# 16_USB_HUB_GL3510.net
KiCad netlist of a schematic drawn in Altium Designer
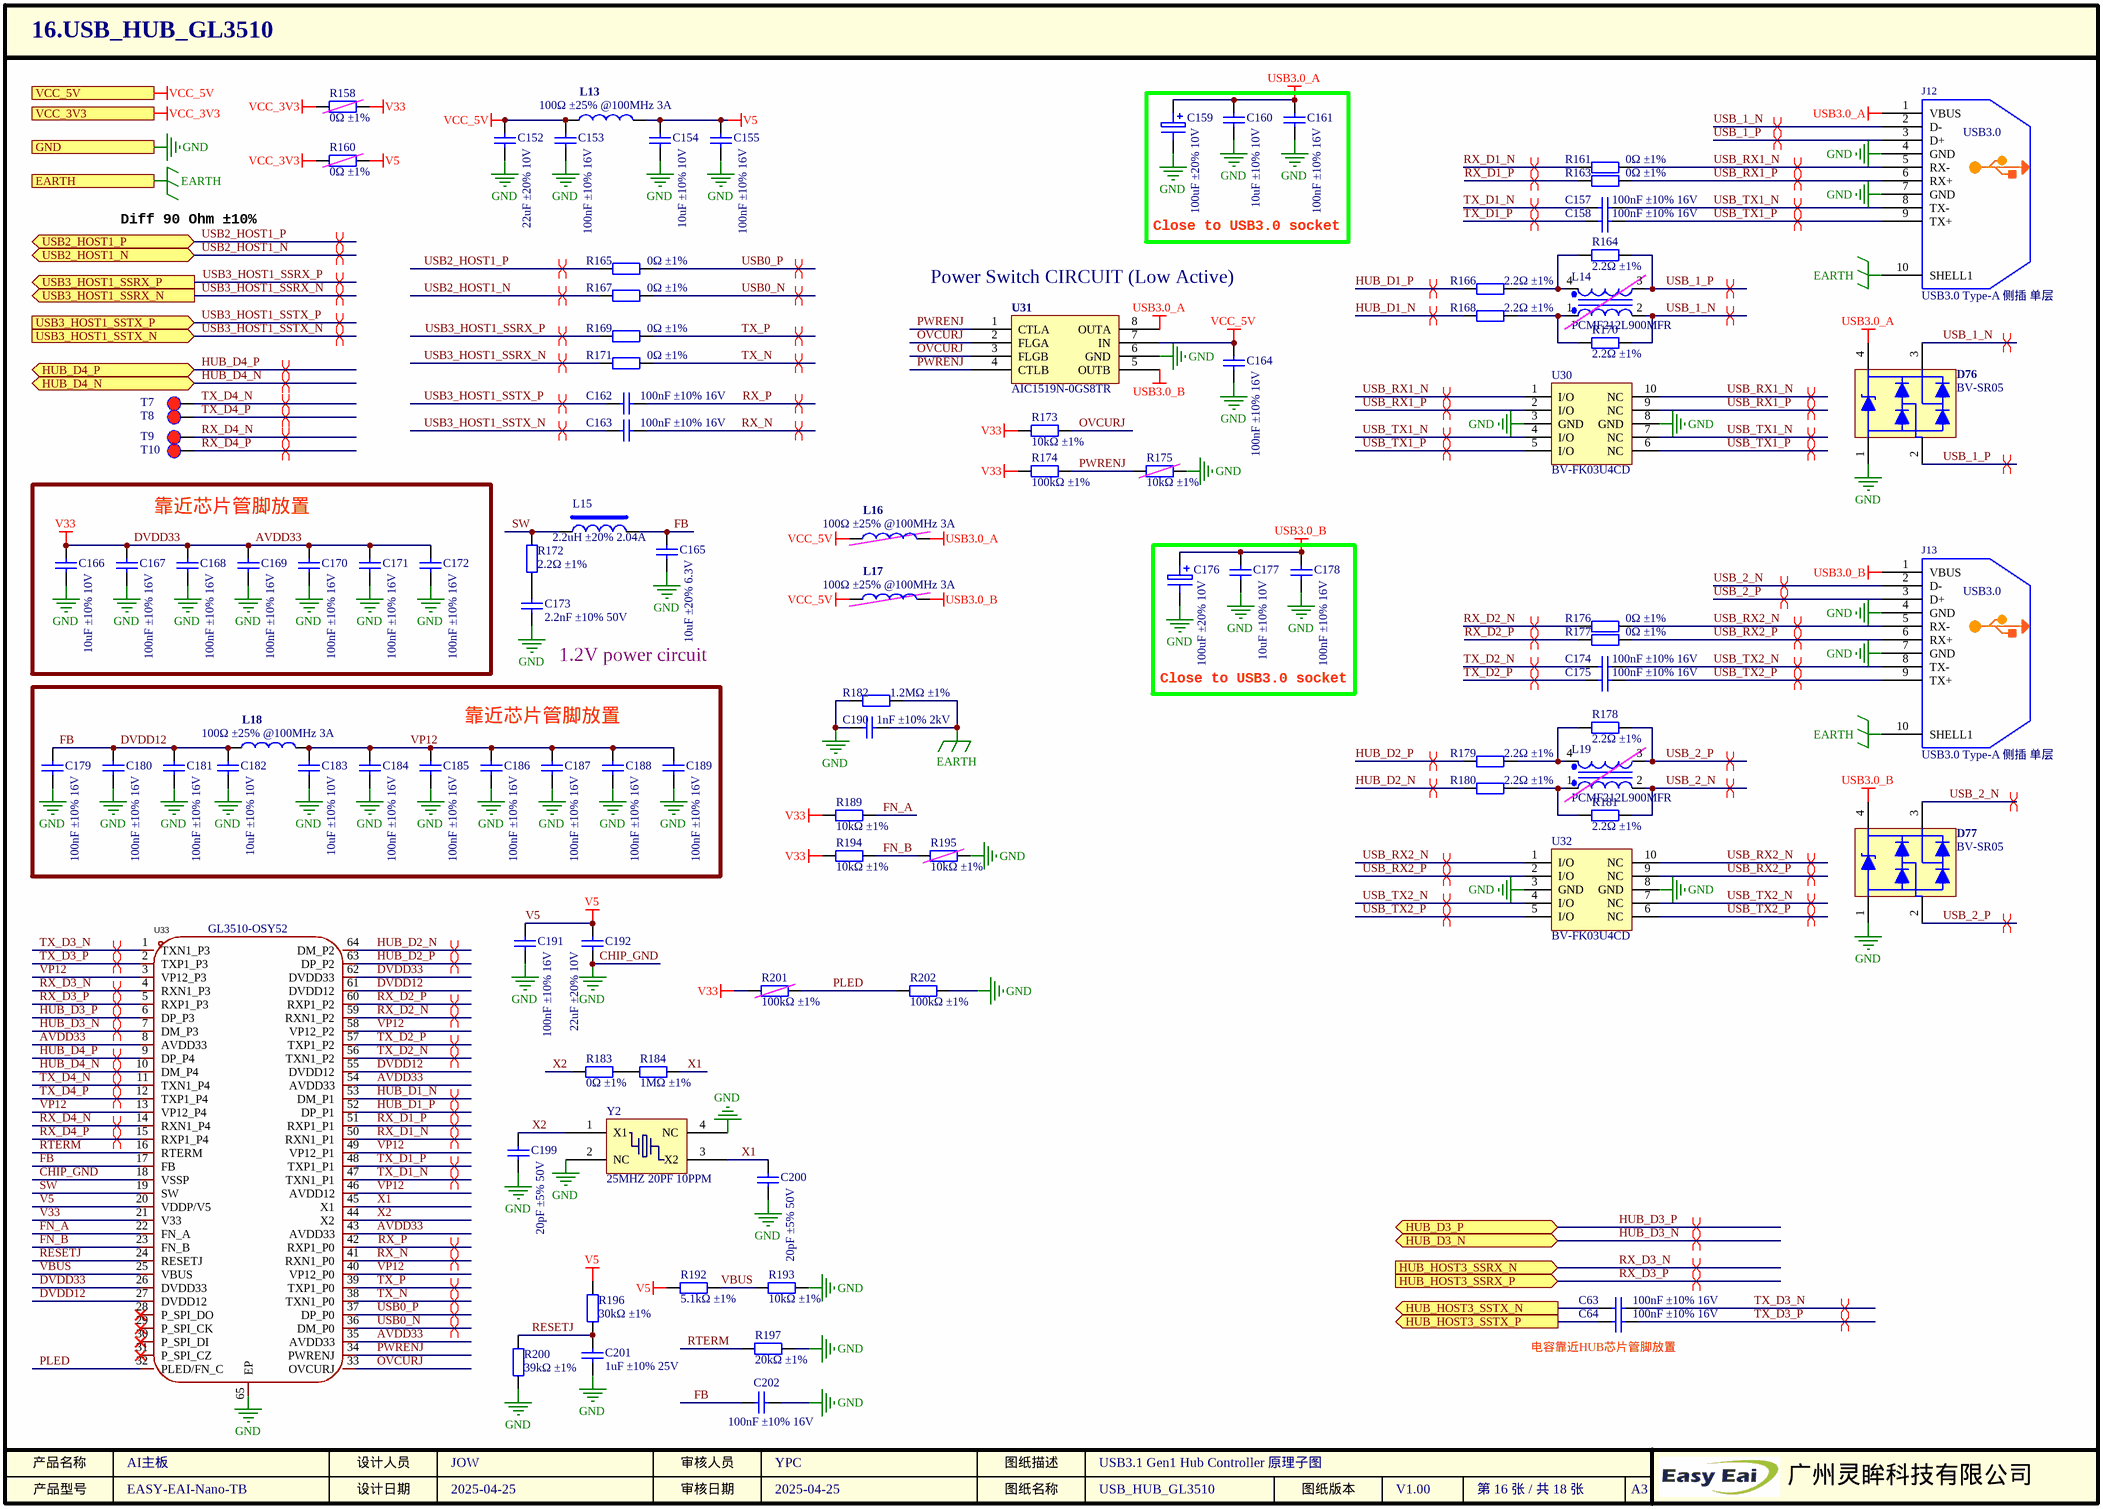
[diagram p0: 16.USB_HUB_GL3510.SchDoc]

(export (version "E")
  (design (tool "Eeschema 10.0.6"))
  (components
    (comp (ref "C63")
      (value "CL05B104KO5NNNC")
      (footprint "0402_C")
      (description "SPZL000259")
      (fields (field (name "描述") "100nF ±10% 16V"))
      (libsource (lib "altium-import") (part "root_2_0402 100nF ±10% 16V_"))
    )
    (comp (ref "C64")
      (value "CL05B104KO5NNNC")
      (footprint "0402_C")
      (description "SPZL000259")
      (fields (field (name "描述") "100nF ±10% 16V"))
      (libsource (lib "altium-import") (part "root_2_0402 100nF ±10% 16V_"))
    )
    (comp (ref "C152")
      (value "CL10A226MP8NUNE")
      (footprint "0603_C")
      (description "SPZL000315")
      (fields (field (name "描述") "22uF ±20% 10V"))
      (libsource (lib "CAP_EASY-EAI") (part "0603 22uF ±20% 10V"))
    )
    (comp (ref "C153")
      (value "CL05B104KO5NNNC")
      (footprint "0402_C")
      (description "SPZL000259")
      (fields (field (name "描述") "100nF ±10% 16V"))
      (libsource (lib "altium-import") (part "root_3_0402 100nF ±10% 16V_"))
    )
    (comp (ref "C154")
      (value "CL10A106KP8NNNC")
      (footprint "0603_C")
      (description "SPZL000260")
      (fields (field (name "描述") "10uF ±10% 10V"))
      (libsource (lib "CAP_EASY-EAI") (part "0603 10uF ±10% 10V"))
    )
    (comp (ref "C155")
      (value "CL05B104KO5NNNC")
      (footprint "0402_C")
      (description "SPZL000259")
      (fields (field (name "描述") "100nF ±10% 16V"))
      (libsource (lib "altium-import") (part "root_3_0402 100nF ±10% 16V_"))
    )
    (comp (ref "C157")
      (value "CL05B104KO5NNNC")
      (footprint "0402_C")
      (description "SPZL000259")
      (fields (field (name "描述") "100nF ±10% 16V"))
      (libsource (lib "altium-import") (part "root_0_0402 100nF ±10% 16V_"))
    )
    (comp (ref "C158")
      (value "CL05B104KO5NNNC")
      (footprint "0402_C")
      (description "SPZL000259")
      (fields (field (name "描述") "100nF ±10% 16V"))
      (libsource (lib "altium-import") (part "root_0_0402 100nF ±10% 16V_"))
    )
    (comp (ref "C159")
      (value "RVT1A101M0505")
      (footprint "SMD,D5xL5.4mm")
      (description "SPZL000265")
      (fields (field (name "描述") "100uF ±20% 10V"))
      (libsource (lib "altium-import") (part "root_0_电解电容 100uF ±20% 10V_"))
    )
    (comp (ref "C160")
      (value "CL10A106KP8NNNC")
      (footprint "0603_C")
      (description "SPZL000260")
      (fields (field (name "描述") "10uF ±10% 10V"))
      (libsource (lib "altium-import") (part "root_1_0603 10uF ±10% 10V_"))
    )
    (comp (ref "C161")
      (value "CL05B104KO5NNNC")
      (footprint "0402_C")
      (description "SPZL000259")
      (fields (field (name "描述") "100nF ±10% 16V"))
      (libsource (lib "altium-import") (part "root_1_0402 100nF ±10% 16V_"))
    )
    (comp (ref "C162")
      (value "CL05B104KO5NNNC")
      (footprint "0402_C")
      (description "SPZL000259")
      (fields (field (name "描述") "100nF ±10% 16V"))
      (libsource (lib "altium-import") (part "root_2_0402 100nF ±10% 16V_"))
    )
    (comp (ref "C163")
      (value "CL05B104KO5NNNC")
      (footprint "0402_C")
      (description "SPZL000259")
      (fields (field (name "描述") "100nF ±10% 16V"))
      (libsource (lib "altium-import") (part "root_2_0402 100nF ±10% 16V_"))
    )
    (comp (ref "C164")
      (value "CL05B104KO5NNNC")
      (footprint "0402_C")
      (description "SPZL000259")
      (fields (field (name "描述") "100nF ±10% 16V"))
      (libsource (lib "altium-import") (part "root_1_0402 100nF ±10% 16V_"))
    )
    (comp (ref "C165")
      (value "CL05A106MQ5NUNC")
      (footprint "0402_C")
      (description "SPZL000269")
      (fields (field (name "描述") "10uF ±20% 6.3V"))
      (libsource (lib "CAP_EASY-EAI") (part "0402 10uF ±20% 6.3V"))
    )
    (comp (ref "C166")
      (value "CL10A106KP8NNNC")
      (footprint "0603_C")
      (description "SPZL000260")
      (fields (field (name "描述") "10uF ±10% 10V"))
      (libsource (lib "CAP_EASY-EAI") (part "0603 10uF ±10% 10V"))
    )
    (comp (ref "C167")
      (value "CL05B104KO5NNNC")
      (footprint "0402_C")
      (description "SPZL000259")
      (fields (field (name "描述") "100nF ±10% 16V"))
      (libsource (lib "altium-import") (part "root_3_0402 100nF ±10% 16V_"))
    )
    (comp (ref "C168")
      (value "CL05B104KO5NNNC")
      (footprint "0402_C")
      (description "SPZL000259")
      (fields (field (name "描述") "100nF ±10% 16V"))
      (libsource (lib "altium-import") (part "root_3_0402 100nF ±10% 16V_"))
    )
    (comp (ref "C169")
      (value "CL05B104KO5NNNC")
      (footprint "0402_C")
      (description "SPZL000259")
      (fields (field (name "描述") "100nF ±10% 16V"))
      (libsource (lib "altium-import") (part "root_3_0402 100nF ±10% 16V_"))
    )
    (comp (ref "C170")
      (value "CL05B104KO5NNNC")
      (footprint "0402_C")
      (description "SPZL000259")
      (fields (field (name "描述") "100nF ±10% 16V"))
      (libsource (lib "altium-import") (part "root_3_0402 100nF ±10% 16V_"))
    )
    (comp (ref "C171")
      (value "CL05B104KO5NNNC")
      (footprint "0402_C")
      (description "SPZL000259")
      (fields (field (name "描述") "100nF ±10% 16V"))
      (libsource (lib "altium-import") (part "root_3_0402 100nF ±10% 16V_"))
    )
    (comp (ref "C172")
      (value "CL05B104KO5NNNC")
      (footprint "0402_C")
      (description "SPZL000259")
      (fields (field (name "描述") "100nF ±10% 16V"))
      (libsource (lib "altium-import") (part "root_3_0402 100nF ±10% 16V_"))
    )
    (comp (ref "C173")
      (value "0402B222K500NT")
      (footprint "0402_C")
      (description "SPZL000399")
      (fields (field (name "描述") "2.2nF ±10% 50V"))
      (libsource (lib "CAP_EASY-EAI") (part "0402 2.2nF ±10% 50V"))
    )
    (comp (ref "C174")
      (value "CL05B104KO5NNNC")
      (footprint "0402_C")
      (description "SPZL000259")
      (fields (field (name "描述") "100nF ±10% 16V"))
      (libsource (lib "altium-import") (part "root_0_0402 100nF ±10% 16V_"))
    )
    (comp (ref "C175")
      (value "CL05B104KO5NNNC")
      (footprint "0402_C")
      (description "SPZL000259")
      (fields (field (name "描述") "100nF ±10% 16V"))
      (libsource (lib "altium-import") (part "root_0_0402 100nF ±10% 16V_"))
    )
    (comp (ref "C176")
      (value "RVT1A101M0505")
      (footprint "SMD,D5xL5.4mm")
      (description "SPZL000265")
      (fields (field (name "描述") "100uF ±20% 10V"))
      (libsource (lib "altium-import") (part "root_0_电解电容 100uF ±20% 10V_"))
    )
    (comp (ref "C177")
      (value "CL10A106KP8NNNC")
      (footprint "0603_C")
      (description "SPZL000260")
      (fields (field (name "描述") "10uF ±10% 10V"))
      (libsource (lib "altium-import") (part "root_1_0603 10uF ±10% 10V_"))
    )
    (comp (ref "C178")
      (value "CL05B104KO5NNNC")
      (footprint "0402_C")
      (description "SPZL000259")
      (fields (field (name "描述") "100nF ±10% 16V"))
      (libsource (lib "altium-import") (part "root_1_0402 100nF ±10% 16V_"))
    )
    (comp (ref "C179")
      (value "CL05B104KO5NNNC")
      (footprint "0402_C")
      (description "SPZL000259")
      (fields (field (name "描述") "100nF ±10% 16V"))
      (libsource (lib "altium-import") (part "root_3_0402 100nF ±10% 16V_"))
    )
    (comp (ref "C180")
      (value "CL05B104KO5NNNC")
      (footprint "0402_C")
      (description "SPZL000259")
      (fields (field (name "描述") "100nF ±10% 16V"))
      (libsource (lib "altium-import") (part "root_3_0402 100nF ±10% 16V_"))
    )
    (comp (ref "C181")
      (value "CL05B104KO5NNNC")
      (footprint "0402_C")
      (description "SPZL000259")
      (fields (field (name "描述") "100nF ±10% 16V"))
      (libsource (lib "altium-import") (part "root_3_0402 100nF ±10% 16V_"))
    )
    (comp (ref "C182")
      (value "CL10A106KP8NNNC")
      (footprint "0603_C")
      (description "SPZL000260")
      (fields (field (name "描述") "10uF ±10% 10V"))
      (libsource (lib "CAP_EASY-EAI") (part "0603 10uF ±10% 10V"))
    )
    (comp (ref "C183")
      (value "CL10A106KP8NNNC")
      (footprint "0603_C")
      (description "SPZL000260")
      (fields (field (name "描述") "10uF ±10% 10V"))
      (libsource (lib "CAP_EASY-EAI") (part "0603 10uF ±10% 10V"))
    )
    (comp (ref "C184")
      (value "CL05B104KO5NNNC")
      (footprint "0402_C")
      (description "SPZL000259")
      (fields (field (name "描述") "100nF ±10% 16V"))
      (libsource (lib "altium-import") (part "root_3_0402 100nF ±10% 16V_"))
    )
    (comp (ref "C185")
      (value "CL05B104KO5NNNC")
      (footprint "0402_C")
      (description "SPZL000259")
      (fields (field (name "描述") "100nF ±10% 16V"))
      (libsource (lib "altium-import") (part "root_3_0402 100nF ±10% 16V_"))
    )
    (comp (ref "C186")
      (value "CL05B104KO5NNNC")
      (footprint "0402_C")
      (description "SPZL000259")
      (fields (field (name "描述") "100nF ±10% 16V"))
      (libsource (lib "altium-import") (part "root_3_0402 100nF ±10% 16V_"))
    )
    (comp (ref "C187")
      (value "CL05B104KO5NNNC")
      (footprint "0402_C")
      (description "SPZL000259")
      (fields (field (name "描述") "100nF ±10% 16V"))
      (libsource (lib "altium-import") (part "root_3_0402 100nF ±10% 16V_"))
    )
    (comp (ref "C188")
      (value "CL05B104KO5NNNC")
      (footprint "0402_C")
      (description "SPZL000259")
      (fields (field (name "描述") "100nF ±10% 16V"))
      (libsource (lib "altium-import") (part "root_3_0402 100nF ±10% 16V_"))
    )
    (comp (ref "C189")
      (value "CL05B104KO5NNNC")
      (footprint "0402_C")
      (description "SPZL000259")
      (fields (field (name "描述") "100nF ±10% 16V"))
      (libsource (lib "altium-import") (part "root_3_0402 100nF ±10% 16V_"))
    )
    (comp (ref "C190")
      (value "CC1206KKX7RDBB102")
      (footprint "1206_C")
      (description "SPZL000332")
      (fields (field (name "描述") "1nF ±10% 2kV"))
      (libsource (lib "altium-import") (part "root_0_1206 1nF ±10% 2kV_"))
    )
    (comp (ref "C191")
      (value "CL05B104KO5NNNC")
      (footprint "0402_C")
      (description "SPZL000259")
      (fields (field (name "描述") "100nF ±10% 16V"))
      (libsource (lib "altium-import") (part "root_3_0402 100nF ±10% 16V_"))
    )
    (comp (ref "C192")
      (value "CL10A226MP8NUNE")
      (footprint "0603_C")
      (description "SPZL000315")
      (fields (field (name "描述") "22uF ±20% 10V"))
      (libsource (lib "CAP_EASY-EAI") (part "0603 22uF ±20% 10V"))
    )
    (comp (ref "C199")
      (value "0402CG200J500NT")
      (footprint "0402_C")
      (description "SPZL000398")
      (fields (field (name "描述") "20pF ±5% 50V"))
      (libsource (lib "CAP_EASY-EAI") (part "0402 20pF ±5% 50V"))
    )
    (comp (ref "C200")
      (value "0402CG200J500NT")
      (footprint "0402_C")
      (description "SPZL000398")
      (fields (field (name "描述") "20pF ±5% 50V"))
      (libsource (lib "CAP_EASY-EAI") (part "0402 20pF ±5% 50V"))
    )
    (comp (ref "C201")
      (value "CL05A105KA5NQNC")
      (footprint "0402_C")
      (description "SPZL000337")
      (fields (field (name "描述") "1uF ±10% 25V"))
      (libsource (lib "CAP_EASY-EAI") (part "0402 1uF ±10% 25V"))
    )
    (comp (ref "C202")
      (value "CL05B104KO5NNNC")
      (footprint "0402_C")
      (description "SPZL000259")
      (fields (field (name "描述") "100nF ±10% 16V"))
      (libsource (lib "altium-import") (part "root_2_0402 100nF ±10% 16V_"))
    )
    (comp (ref "D76")
      (value "BV-SR05")
      (footprint "SOT-143")
      (description "SPZL000616")
      (fields (field (name "型号") "BV-SR05"))
      (libsource (lib "ESD_EASY-EAI") (part "TVS BV-SR05"))
    )
    (comp (ref "D77")
      (value "BV-SR05")
      (footprint "SOT-143")
      (description "SPZL000616")
      (fields (field (name "型号") "BV-SR05"))
      (libsource (lib "ESD_EASY-EAI") (part "TVS BV-SR05"))
    )
    (comp (ref "J12")
      (value "U231-091N-4BLCC14-S5")
      (footprint "USB3.0-A-TH_U231-091N-4BLCC14-S-5")
      (description "SPZL001065")
      (fields (field (name "描述") "USB3.0 Type-A 侧插 单层"))
      (libsource (lib "EASY-EAI-Nano-TB V1.01") (part "USB3.0 Type-A 侧插 单层"))
    )
    (comp (ref "J13")
      (value "U231-091N-4BLCC14-S5")
      (footprint "USB3.0-A-TH_U231-091N-4BLCC14-S-5")
      (description "SPZL001065")
      (fields (field (name "描述") "USB3.0 Type-A 侧插 单层"))
      (libsource (lib "EASY-EAI-Nano-TB V1.01") (part "USB3.0 Type-A 侧插 单层"))
    )
    (comp (ref "L13")
      (value "MPZ1608S101ATAH0")
      (footprint "0603_R")
      (description "SPZL000753")
      (fields (field (name "描述") "100Ω ±25% @100MHz 3A"))
      (libsource (lib "Inductor_EASY-EAI") (part "100Ω ±25% @100MHz 3A"))
    )
    (comp (ref "L14")
      (value "PCMF212L900MFR")
      (footprint "SMD2012")
      (description "SPZL001149")
      (fields (field (name "型号") "PCMF212L900MFR"))
      (libsource (lib "ESD_EASY-EAI") (part "共模电感 PCMF212L900MFR"))
    )
    (comp (ref "L15")
      (value "VLS252012HBX-2R2M-1")
      (footprint "IND_252012")
      (description "SPZL000205")
      (fields (field (name "描述") "2.2uH ±20% 2.04A"))
      (libsource (lib "Inductor_EASY-EAI") (part "2.2uH ±20% 2.04A"))
    )
    (comp (ref "L16")
      (value "MPZ1608S101ATAH0")
      (footprint "0603_R")
      (description "SPZL000753")
      (fields (field (name "描述") "100Ω ±25% @100MHz 3A"))
      (libsource (lib "Inductor_EASY-EAI") (part "100Ω ±25% @100MHz 3A"))
    )
    (comp (ref "L17")
      (value "MPZ1608S101ATAH0")
      (footprint "0603_R")
      (description "SPZL000753")
      (fields (field (name "描述") "100Ω ±25% @100MHz 3A"))
      (libsource (lib "Inductor_EASY-EAI") (part "100Ω ±25% @100MHz 3A"))
    )
    (comp (ref "L18")
      (value "MPZ1608S101ATAH0")
      (footprint "0603_R")
      (description "SPZL000753")
      (fields (field (name "描述") "100Ω ±25% @100MHz 3A"))
      (libsource (lib "Inductor_EASY-EAI") (part "100Ω ±25% @100MHz 3A"))
    )
    (comp (ref "L19")
      (value "PCMF212L900MFR")
      (footprint "SMD2012")
      (description "SPZL001149")
      (fields (field (name "型号") "PCMF212L900MFR"))
      (libsource (lib "ESD_EASY-EAI") (part "共模电感 PCMF212L900MFR"))
    )
    (comp (ref "R158")
      (value "0805W8F0000T5E")
      (footprint "0805_R")
      (description "SPZL000350")
      (fields (field (name "描述") "0Ω ±1%"))
      (libsource (lib "RES_EASY-EAI") (part "0805 0Ω ±1%"))
    )
    (comp (ref "R160")
      (value "0805W8F0000T5E")
      (footprint "0805_R")
      (description "SPZL000350")
      (fields (field (name "描述") "0Ω ±1%"))
      (libsource (lib "RES_EASY-EAI") (part "0805 0Ω ±1%"))
    )
    (comp (ref "R161")
      (value "0402WGF0000TCE")
      (footprint "0402_R")
      (description "SPZL000276")
      (fields (field (name "描述") "0Ω ±1%"))
      (libsource (lib "RES_EASY-EAI") (part "0402 0Ω ±1%"))
    )
    (comp (ref "R163")
      (value "0402WGF0000TCE")
      (footprint "0402_R")
      (description "SPZL000276")
      (fields (field (name "描述") "0Ω ±1%"))
      (libsource (lib "RES_EASY-EAI") (part "0402 0Ω ±1%"))
    )
    (comp (ref "R164")
      (value "0402WGF220KTCE")
      (footprint "0402_R")
      (description "SPZL000327")
      (fields (field (name "描述") "2.2Ω ±1%"))
      (libsource (lib "RES_EASY-EAI") (part "0402 2.2Ω ±1%"))
    )
    (comp (ref "R165")
      (value "0402WGF0000TCE")
      (footprint "0402_R")
      (description "SPZL000276")
      (fields (field (name "描述") "0Ω ±1%"))
      (libsource (lib "RES_EASY-EAI") (part "0402 0Ω ±1%"))
    )
    (comp (ref "R166")
      (value "0402WGF220KTCE")
      (footprint "0402_R")
      (description "SPZL000327")
      (fields (field (name "描述") "2.2Ω ±1%"))
      (libsource (lib "RES_EASY-EAI") (part "0402 2.2Ω ±1%"))
    )
    (comp (ref "R167")
      (value "0402WGF0000TCE")
      (footprint "0402_R")
      (description "SPZL000276")
      (fields (field (name "描述") "0Ω ±1%"))
      (libsource (lib "RES_EASY-EAI") (part "0402 0Ω ±1%"))
    )
    (comp (ref "R168")
      (value "0402WGF220KTCE")
      (footprint "0402_R")
      (description "SPZL000327")
      (fields (field (name "描述") "2.2Ω ±1%"))
      (libsource (lib "RES_EASY-EAI") (part "0402 2.2Ω ±1%"))
    )
    (comp (ref "R169")
      (value "0402WGF0000TCE")
      (footprint "0402_R")
      (description "SPZL000276")
      (fields (field (name "描述") "0Ω ±1%"))
      (libsource (lib "RES_EASY-EAI") (part "0402 0Ω ±1%"))
    )
    (comp (ref "R170")
      (value "0402WGF220KTCE")
      (footprint "0402_R")
      (description "SPZL000327")
      (fields (field (name "描述") "2.2Ω ±1%"))
      (libsource (lib "RES_EASY-EAI") (part "0402 2.2Ω ±1%"))
    )
    (comp (ref "R171")
      (value "0402WGF0000TCE")
      (footprint "0402_R")
      (description "SPZL000276")
      (fields (field (name "描述") "0Ω ±1%"))
      (libsource (lib "RES_EASY-EAI") (part "0402 0Ω ±1%"))
    )
    (comp (ref "R172")
      (value "0402WGF220KTCE")
      (footprint "0402_R")
      (description "SPZL000327")
      (fields (field (name "描述") "2.2Ω ±1%"))
      (libsource (lib "") (part "0402 2.2Ω ±1%_1"))
    )
    (comp (ref "R173")
      (value "0402WGF1002TCE")
      (footprint "0402_R")
      (description "SPZL000271")
      (fields (field (name "描述") "10kΩ ±1%"))
      (libsource (lib "") (part "0402 10kΩ ±1%_1"))
    )
    (comp (ref "R174")
      (value "0402WGF1003TCE")
      (footprint "0402_R")
      (description "SPZL000282")
      (fields (field (name "描述") "100kΩ ±1%"))
      (libsource (lib "RES_EASY-EAI") (part "0402 100kΩ ±1%"))
    )
    (comp (ref "R175")
      (value "0402WGF1002TCE")
      (footprint "0402_R")
      (description "SPZL000271")
      (fields (field (name "描述") "10kΩ ±1%"))
      (libsource (lib "RES_EASY-EAI") (part "0402 10kΩ ±1%"))
    )
    (comp (ref "R176")
      (value "0402WGF0000TCE")
      (footprint "0402_R")
      (description "SPZL000276")
      (fields (field (name "描述") "0Ω ±1%"))
      (libsource (lib "RES_EASY-EAI") (part "0402 0Ω ±1%"))
    )
    (comp (ref "R177")
      (value "0402WGF0000TCE")
      (footprint "0402_R")
      (description "SPZL000276")
      (fields (field (name "描述") "0Ω ±1%"))
      (libsource (lib "RES_EASY-EAI") (part "0402 0Ω ±1%"))
    )
    (comp (ref "R178")
      (value "0402WGF220KTCE")
      (footprint "0402_R")
      (description "SPZL000327")
      (fields (field (name "描述") "2.2Ω ±1%"))
      (libsource (lib "RES_EASY-EAI") (part "0402 2.2Ω ±1%"))
    )
    (comp (ref "R179")
      (value "0402WGF220KTCE")
      (footprint "0402_R")
      (description "SPZL000327")
      (fields (field (name "描述") "2.2Ω ±1%"))
      (libsource (lib "RES_EASY-EAI") (part "0402 2.2Ω ±1%"))
    )
    (comp (ref "R180")
      (value "0402WGF220KTCE")
      (footprint "0402_R")
      (description "SPZL000327")
      (fields (field (name "描述") "2.2Ω ±1%"))
      (libsource (lib "RES_EASY-EAI") (part "0402 2.2Ω ±1%"))
    )
    (comp (ref "R181")
      (value "0402WGF220KTCE")
      (footprint "0402_R")
      (description "SPZL000327")
      (fields (field (name "描述") "2.2Ω ±1%"))
      (libsource (lib "RES_EASY-EAI") (part "0402 2.2Ω ±1%"))
    )
    (comp (ref "R182")
      (value "1206W4F1204T5E")
      (footprint "1206_R")
      (description "SPZL000388")
      (fields (field (name "描述") "1.2MΩ ±1%"))
      (libsource (lib "RES_EASY-EAI") (part "1206 1.2MΩ ±1%"))
    )
    (comp (ref "R183")
      (value "0402WGF0000TCE")
      (footprint "0402_R")
      (description "SPZL000276")
      (fields (field (name "描述") "0Ω ±1%"))
      (libsource (lib "RES_EASY-EAI") (part "0402 0Ω ±1%"))
    )
    (comp (ref "R184")
      (value "RC-02W1004FT")
      (footprint "0402_R")
      (description "SPZL000301")
      (fields (field (name "描述") "1MΩ ±1%"))
      (libsource (lib "RES_EASY-EAI") (part "0402 1MΩ ±1%"))
    )
    (comp (ref "R189")
      (value "0402WGF1002TCE")
      (footprint "0402_R")
      (description "SPZL000271")
      (fields (field (name "描述") "10kΩ ±1%"))
      (libsource (lib "RES_EASY-EAI") (part "0402 10kΩ ±1%"))
    )
    (comp (ref "R192")
      (value "0402WGF5101TCE")
      (footprint "0402_R")
      (description "SPZL000270")
      (fields (field (name "描述") "5.1kΩ ±1%"))
      (libsource (lib "RES_EASY-EAI") (part "0402 5.1kΩ ±1%"))
    )
    (comp (ref "R193")
      (value "0402WGF1002TCE")
      (footprint "0402_R")
      (description "SPZL000271")
      (fields (field (name "描述") "10kΩ ±1%"))
      (libsource (lib "RES_EASY-EAI") (part "0402 10kΩ ±1%"))
    )
    (comp (ref "R194")
      (value "0402WGF1002TCE")
      (footprint "0402_R")
      (description "SPZL000271")
      (fields (field (name "描述") "10kΩ ±1%"))
      (libsource (lib "RES_EASY-EAI") (part "0402 10kΩ ±1%"))
    )
    (comp (ref "R195")
      (value "0402WGF1002TCE")
      (footprint "0402_R")
      (description "SPZL000271")
      (fields (field (name "描述") "10kΩ ±1%"))
      (libsource (lib "RES_EASY-EAI") (part "0402 10kΩ ±1%"))
    )
    (comp (ref "R196")
      (value "NQ02WGF3002TCE")
      (footprint "0402_R")
      (description "SPZL000323")
      (fields (field (name "描述") "30kΩ ±1%"))
      (libsource (lib "RES_EASY-EAI") (part "0402 30kΩ ±1%"))
    )
    (comp (ref "R197")
      (value "0402WGF2002TCE")
      (footprint "0402_R")
      (description "SPZL000349")
      (fields (field (name "描述") "20kΩ ±1%"))
      (libsource (lib "RES_EASY-EAI") (part "0402 20kΩ ±1%"))
    )
    (comp (ref "R200")
      (value "RC0402FR-0739KL")
      (footprint "0402_R")
      (description "SPZL001271")
      (fields (field (name "描述") "39kΩ ±1%"))
      (libsource (lib "RES_EASY-EAI") (part "0402 39kΩ ±1%"))
    )
    (comp (ref "R201")
      (value "0402WGF1003TCE")
      (footprint "0402_R")
      (description "SPZL000282")
      (fields (field (name "描述") "100kΩ ±1%"))
      (libsource (lib "RES_EASY-EAI") (part "0402 100kΩ ±1%"))
    )
    (comp (ref "R202")
      (value "0402WGF1003TCE")
      (footprint "0402_R")
      (description "SPZL000282")
      (fields (field (name "描述") "100kΩ ±1%"))
      (libsource (lib "RES_EASY-EAI") (part "0402 100kΩ ±1%"))
    )
    (comp (ref "T7")
      (value "TEST-DOT")
      (footprint "PAD-25/40")
      (libsource (lib "Other_EASY-EAI") (part "TEST-DOT"))
    )
    (comp (ref "T8")
      (value "TEST-DOT")
      (footprint "PAD-25/40")
      (libsource (lib "Other_EASY-EAI") (part "TEST-DOT"))
    )
    (comp (ref "T9")
      (value "TEST-DOT")
      (footprint "PAD-25/40")
      (libsource (lib "Other_EASY-EAI") (part "TEST-DOT"))
    )
    (comp (ref "T10")
      (value "TEST-DOT")
      (footprint "PAD-25/40")
      (libsource (lib "Other_EASY-EAI") (part "TEST-DOT"))
    )
    (comp (ref "U30")
      (value "ESD BV-FK03U4CD")
      (footprint "UDFN-10")
      (description "SPZL000610")
      (fields (field (name "型号") "BV-FK03U4CD"))
      (libsource (lib "ESD_EASY-EAI") (part "ESD BV-FK03U4CD"))
    )
    (comp (ref "U31")
      (value "AIC1519N-0GS8TR")
      (footprint "SOP-8")
      (description "SPZL001272")
      (fields (field (name "型号") "AIC1519N-0GS8TR"))
      (libsource (lib "IC_EASY-EAI") (part "AIC1519N-0GS8TR"))
    )
    (comp (ref "U32")
      (value "ESD BV-FK03U4CD")
      (footprint "UDFN-10")
      (description "SPZL000610")
      (fields (field (name "型号") "BV-FK03U4CD"))
      (libsource (lib "ESD_EASY-EAI") (part "ESD BV-FK03U4CD"))
    )
    (comp (ref "U33")
      (value "GL3510-OSY52")
      (footprint "QFN-64_L8.0-W8.0-P0.40-BL-EP5.4")
      (description "SPZL001270")
      (libsource (lib "IC_EASY-EAI") (part "GL3510-OSY52"))
    )
    (comp (ref "Y2")
      (value "X322525MSB4SI")
      (footprint "SMD-3225_4P")
      (description "SPZL000475")
      (fields (field (name "描述") "25MHZ 20PF 10PPM"))
      (libsource (lib "XTAL_EASY-EAI") (part "25MHZ 20PF 10PPM"))
    )
  )
  (nets
    (net (code "1") (name "/DVDD12") (class "Default")
      (node (ref "C165") (pin "2") (pinfunction "2_2") (pintype "passive"))
      (node (ref "C179") (pin "1") (pinfunction "1_1") (pintype "passive"))
      (node (ref "C180") (pin "1") (pinfunction "1_1") (pintype "passive"))
      (node (ref "C181") (pin "1") (pinfunction "1_1") (pintype "passive"))
      (node (ref "C182") (pin "1") (pinfunction "1_1") (pintype "passive"))
      (node (ref "C202") (pin "2") (pinfunction "2_2") (pintype "passive"))
      (node (ref "L15") (pin "2") (pinfunction "2_2") (pintype "passive"))
      (node (ref "L18") (pin "1") (pinfunction "1_1") (pintype "passive"))
      (node (ref "U33") (pin "17") (pinfunction "FB_17") (pintype "passive"))
      (node (ref "U33") (pin "27") (pinfunction "DVDD12_27") (pintype "passive"))
      (node (ref "U33") (pin "55") (pinfunction "DVDD12_55") (pintype "passive"))
      (node (ref "U33") (pin "61") (pinfunction "DVDD12_61") (pintype "passive"))
    )
    (net (code "2") (name "/FN_A") (class "Default")
      (node (ref "R189") (pin "1") (pinfunction "1_1") (pintype "passive"))
      (node (ref "U33") (pin "22") (pinfunction "FN_A_22") (pintype "passive"))
    )
    (net (code "3") (name "/FN_B") (class "Default")
      (node (ref "R194") (pin "1") (pinfunction "1_1") (pintype "passive"))
      (node (ref "R195") (pin "2") (pinfunction "2_2") (pintype "passive"))
      (node (ref "U33") (pin "23") (pinfunction "FN_B_23") (pintype "passive"))
    )
    (net (code "4") (name "/HUB_D1_N") (class "Default")
      (node (ref "R168") (pin "1") (pinfunction "1_1") (pintype "passive"))
      (node (ref "U33") (pin "53") (pinfunction "DM_P1_53") (pintype "passive"))
    )
    (net (code "5") (name "/HUB_D1_P") (class "Default")
      (node (ref "R166") (pin "1") (pinfunction "1_1") (pintype "passive"))
      (node (ref "U33") (pin "52") (pinfunction "DP_P1_52") (pintype "passive"))
    )
    (net (code "6") (name "/HUB_D2_N") (class "Default")
      (node (ref "R180") (pin "1") (pinfunction "1_1") (pintype "passive"))
      (node (ref "U33") (pin "64") (pinfunction "DM_P2_64") (pintype "passive"))
    )
    (net (code "7") (name "/HUB_D2_P") (class "Default")
      (node (ref "R179") (pin "1") (pinfunction "1_1") (pintype "passive"))
      (node (ref "U33") (pin "63") (pinfunction "DP_P2_63") (pintype "passive"))
    )
    (net (code "8") (name "/HUB_D3_N") (class "Default")
      (node (ref "U33") (pin "7") (pinfunction "DM_P3_7") (pintype "passive"))
    )
    (net (code "9") (name "/HUB_D3_P") (class "Default")
      (node (ref "U33") (pin "6") (pinfunction "DP_P3_6") (pintype "passive"))
    )
    (net (code "10") (name "/HUB_D4_N") (class "Default")
      (node (ref "U33") (pin "10") (pinfunction "DM_P4_10") (pintype "passive"))
    )
    (net (code "11") (name "/HUB_D4_P") (class "Default")
      (node (ref "U33") (pin "9") (pinfunction "DP_P4_9") (pintype "passive"))
    )
    (net (code "12") (name "/HUB_HOST3_SSTX_N") (class "Default")
      (node (ref "C63") (pin "2") (pinfunction "2_2") (pintype "passive"))
    )
    (net (code "13") (name "/HUB_HOST3_SSTX_P") (class "Default")
      (node (ref "C64") (pin "2") (pinfunction "2_2") (pintype "passive"))
    )
    (net (code "14") (name "/OVCURJ") (class "Default")
      (node (ref "R173") (pin "2") (pinfunction "2_2") (pintype "passive"))
      (node (ref "U31") (pin "2") (pinfunction "FLGA_2") (pintype "passive"))
      (node (ref "U31") (pin "3") (pinfunction "FLGB_3") (pintype "power_in"))
      (node (ref "U33") (pin "33") (pinfunction "OVCURJ_33") (pintype "passive"))
    )
    (net (code "15") (name "/PLED") (class "Default")
      (node (ref "R201") (pin "2") (pinfunction "2_2") (pintype "passive"))
      (node (ref "R202") (pin "1") (pinfunction "1_1") (pintype "passive"))
      (node (ref "U33") (pin "32") (pinfunction "PLED/FN_C_32") (pintype "passive"))
    )
    (net (code "16") (name "/PWRENJ") (class "Default")
      (node (ref "R174") (pin "2") (pinfunction "2_2") (pintype "passive"))
      (node (ref "R175") (pin "2") (pinfunction "2_2") (pintype "passive"))
      (node (ref "U31") (pin "1") (pinfunction "CTLA_1") (pintype "passive"))
      (node (ref "U31") (pin "4") (pinfunction "CTLB_4") (pintype "passive"))
      (node (ref "U33") (pin "34") (pinfunction "PWRENJ_34") (pintype "passive"))
    )
    (net (code "17") (name "/RESETJ") (class "Default")
      (node (ref "C201") (pin "2") (pinfunction "2_2") (pintype "passive"))
      (node (ref "R196") (pin "1") (pinfunction "1_1") (pintype "passive"))
      (node (ref "R200") (pin "2") (pinfunction "2_2") (pintype "passive"))
      (node (ref "U33") (pin "24") (pinfunction "RESETJ_24") (pintype "passive"))
    )
    (net (code "18") (name "/RTERM") (class "Default")
      (node (ref "R197") (pin "1") (pinfunction "1_1") (pintype "passive"))
      (node (ref "U33") (pin "16") (pinfunction "RTERM_16") (pintype "passive"))
    )
    (net (code "19") (name "/RX_D1_N") (class "Default")
      (node (ref "R161") (pin "1") (pinfunction "1_1") (pintype "passive"))
      (node (ref "U33") (pin "50") (pinfunction "RXN1_P1_50") (pintype "passive"))
    )
    (net (code "20") (name "/RX_D1_P") (class "Default")
      (node (ref "R163") (pin "1") (pinfunction "1_1") (pintype "passive"))
      (node (ref "U33") (pin "51") (pinfunction "RXP1_P1_51") (pintype "passive"))
    )
    (net (code "21") (name "/RX_D2_N") (class "Default")
      (node (ref "R176") (pin "1") (pinfunction "1_1") (pintype "passive"))
      (node (ref "U33") (pin "59") (pinfunction "RXN1_P2_59") (pintype "passive"))
    )
    (net (code "22") (name "/RX_D2_P") (class "Default")
      (node (ref "R177") (pin "1") (pinfunction "1_1") (pintype "passive"))
      (node (ref "U33") (pin "60") (pinfunction "RXP1_P2_60") (pintype "passive"))
    )
    (net (code "23") (name "/RX_D3_N") (class "Default")
      (node (ref "U33") (pin "4") (pinfunction "RXN1_P3_4") (pintype "passive"))
    )
    (net (code "24") (name "/RX_D3_P") (class "Default")
      (node (ref "U33") (pin "5") (pinfunction "RXP1_P3_5") (pintype "passive"))
    )
    (net (code "25") (name "/RX_D4_N") (class "Default")
      (node (ref "T9") (pin "1") (pinfunction "1_1") (pintype "passive"))
      (node (ref "U33") (pin "14") (pinfunction "RXN1_P4_14") (pintype "passive"))
    )
    (net (code "26") (name "/RX_D4_P") (class "Default")
      (node (ref "T10") (pin "1") (pinfunction "1_1") (pintype "passive"))
      (node (ref "U33") (pin "15") (pinfunction "RXP1_P4_15") (pintype "passive"))
    )
    (net (code "27") (name "/RX_N") (class "Default")
      (node (ref "C163") (pin "1") (pinfunction "1_1") (pintype "passive"))
      (node (ref "U33") (pin "41") (pinfunction "RXN1_P0_41") (pintype "passive"))
    )
    (net (code "28") (name "/RX_P") (class "Default")
      (node (ref "C162") (pin "1") (pinfunction "1_1") (pintype "passive"))
      (node (ref "U33") (pin "42") (pinfunction "RXP1_P0_42") (pintype "passive"))
    )
    (net (code "29") (name "/SW") (class "Default")
      (node (ref "L15") (pin "1") (pinfunction "1_1") (pintype "passive"))
      (node (ref "R172") (pin "2") (pinfunction "2_2") (pintype "passive"))
      (node (ref "U33") (pin "19") (pinfunction "SW_19") (pintype "passive"))
    )
    (net (code "30") (name "/TX_D1_N") (class "Default")
      (node (ref "C157") (pin "1") (pinfunction "1_1") (pintype "passive"))
      (node (ref "U33") (pin "47") (pinfunction "TXN1_P1_47") (pintype "passive"))
    )
    (net (code "31") (name "/TX_D1_P") (class "Default")
      (node (ref "C158") (pin "1") (pinfunction "1_1") (pintype "passive"))
      (node (ref "U33") (pin "48") (pinfunction "TXP1_P1_48") (pintype "passive"))
    )
    (net (code "32") (name "/TX_D2_N") (class "Default")
      (node (ref "C174") (pin "1") (pinfunction "1_1") (pintype "passive"))
      (node (ref "U33") (pin "56") (pinfunction "TXN1_P2_56") (pintype "passive"))
    )
    (net (code "33") (name "/TX_D2_P") (class "Default")
      (node (ref "C175") (pin "1") (pinfunction "1_1") (pintype "passive"))
      (node (ref "U33") (pin "57") (pinfunction "TXP1_P2_57") (pintype "passive"))
    )
    (net (code "34") (name "/TX_D3_N") (class "Default")
      (node (ref "C63") (pin "1") (pinfunction "1_1") (pintype "passive"))
      (node (ref "U33") (pin "1") (pinfunction "TXN1_P3_1") (pintype "passive"))
    )
    (net (code "35") (name "/TX_D3_P") (class "Default")
      (node (ref "C64") (pin "1") (pinfunction "1_1") (pintype "passive"))
      (node (ref "U33") (pin "2") (pinfunction "TXP1_P3_2") (pintype "passive"))
    )
    (net (code "36") (name "/TX_D4_N") (class "Default")
      (node (ref "T7") (pin "1") (pinfunction "1_1") (pintype "passive"))
      (node (ref "U33") (pin "11") (pinfunction "TXN1_P4_11") (pintype "passive"))
    )
    (net (code "37") (name "/TX_D4_P") (class "Default")
      (node (ref "T8") (pin "1") (pinfunction "1_1") (pintype "passive"))
      (node (ref "U33") (pin "12") (pinfunction "TXP1_P4_12") (pintype "passive"))
    )
    (net (code "38") (name "/TX_N") (class "Default")
      (node (ref "R171") (pin "2") (pinfunction "2_2") (pintype "passive"))
      (node (ref "U33") (pin "38") (pinfunction "TXN1_P0_38") (pintype "passive"))
    )
    (net (code "39") (name "/TX_P") (class "Default")
      (node (ref "R169") (pin "2") (pinfunction "2_2") (pintype "passive"))
      (node (ref "U33") (pin "39") (pinfunction "TXP1_P0_39") (pintype "passive"))
    )
    (net (code "40") (name "/USB0_N") (class "Default")
      (node (ref "R167") (pin "2") (pinfunction "2_2") (pintype "passive"))
      (node (ref "U33") (pin "36") (pinfunction "DM_P0_36") (pintype "passive"))
    )
    (net (code "41") (name "/USB0_P") (class "Default")
      (node (ref "R165") (pin "2") (pinfunction "2_2") (pintype "passive"))
      (node (ref "U33") (pin "37") (pinfunction "DP_P0_37") (pintype "passive"))
    )
    (net (code "42") (name "/USB2_HOST1_N") (class "Default")
      (node (ref "R167") (pin "1") (pinfunction "1_1") (pintype "passive"))
    )
    (net (code "43") (name "/USB2_HOST1_P") (class "Default")
      (node (ref "R165") (pin "1") (pinfunction "1_1") (pintype "passive"))
    )
    (net (code "44") (name "/USB3_HOST1_SSRX_N") (class "Default")
      (node (ref "R171") (pin "1") (pinfunction "1_1") (pintype "passive"))
    )
    (net (code "45") (name "/USB3_HOST1_SSRX_P") (class "Default")
      (node (ref "R169") (pin "1") (pinfunction "1_1") (pintype "passive"))
    )
    (net (code "46") (name "/USB3_HOST1_SSTX_N") (class "Default")
      (node (ref "C163") (pin "2") (pinfunction "2_2") (pintype "passive"))
    )
    (net (code "47") (name "/USB3_HOST1_SSTX_P") (class "Default")
      (node (ref "C162") (pin "2") (pinfunction "2_2") (pintype "passive"))
    )
    (net (code "48") (name "/USB_1_N") (class "Default")
      (node (ref "D76") (pin "3") (pintype "passive"))
      (node (ref "J12") (pin "2") (pinfunction "D-_2") (pintype "passive"))
      (node (ref "L14") (pin "2") (pintype "passive"))
      (node (ref "R170") (pin "2") (pinfunction "2_2") (pintype "passive"))
    )
    (net (code "49") (name "/USB_1_P") (class "Default")
      (node (ref "D76") (pin "2") (pintype "passive"))
      (node (ref "J12") (pin "3") (pinfunction "D+_3") (pintype "passive"))
      (node (ref "L14") (pin "3") (pintype "passive"))
      (node (ref "R164") (pin "2") (pinfunction "2_2") (pintype "passive"))
    )
    (net (code "50") (name "/USB_2_N") (class "Default")
      (node (ref "D77") (pin "3") (pintype "passive"))
      (node (ref "J13") (pin "2") (pinfunction "D-_2") (pintype "passive"))
      (node (ref "L19") (pin "2") (pintype "passive"))
      (node (ref "R181") (pin "2") (pinfunction "2_2") (pintype "passive"))
    )
    (net (code "51") (name "/USB_2_P") (class "Default")
      (node (ref "D77") (pin "2") (pintype "passive"))
      (node (ref "J13") (pin "3") (pinfunction "D+_3") (pintype "passive"))
      (node (ref "L19") (pin "3") (pintype "passive"))
      (node (ref "R178") (pin "2") (pinfunction "2_2") (pintype "passive"))
    )
    (net (code "52") (name "/USB_RX1_N") (class "Default")
      (node (ref "J12") (pin "5") (pinfunction "RX-_5") (pintype "passive"))
      (node (ref "R161") (pin "2") (pinfunction "2_2") (pintype "passive"))
      (node (ref "U30") (pin "1") (pinfunction "I/O_1") (pintype "passive"))
      (node (ref "U30") (pin "10") (pinfunction "NC_10") (pintype "passive"))
    )
    (net (code "53") (name "/USB_RX1_P") (class "Default")
      (node (ref "J12") (pin "6") (pinfunction "RX+_6") (pintype "passive"))
      (node (ref "R163") (pin "2") (pinfunction "2_2") (pintype "passive"))
      (node (ref "U30") (pin "2") (pinfunction "I/O_2") (pintype "passive"))
      (node (ref "U30") (pin "9") (pinfunction "NC_9") (pintype "passive"))
    )
    (net (code "54") (name "/USB_RX2_N") (class "Default")
      (node (ref "J13") (pin "5") (pinfunction "RX-_5") (pintype "passive"))
      (node (ref "R176") (pin "2") (pinfunction "2_2") (pintype "passive"))
      (node (ref "U32") (pin "1") (pinfunction "I/O_1") (pintype "passive"))
      (node (ref "U32") (pin "10") (pinfunction "NC_10") (pintype "passive"))
    )
    (net (code "55") (name "/USB_RX2_P") (class "Default")
      (node (ref "J13") (pin "6") (pinfunction "RX+_6") (pintype "passive"))
      (node (ref "R177") (pin "2") (pinfunction "2_2") (pintype "passive"))
      (node (ref "U32") (pin "2") (pinfunction "I/O_2") (pintype "passive"))
      (node (ref "U32") (pin "9") (pinfunction "NC_9") (pintype "passive"))
    )
    (net (code "56") (name "/USB_TX1_N") (class "Default")
      (node (ref "C157") (pin "2") (pinfunction "2_2") (pintype "passive"))
      (node (ref "J12") (pin "8") (pinfunction "TX-_8") (pintype "passive"))
      (node (ref "U30") (pin "4") (pinfunction "I/O_4") (pintype "passive"))
      (node (ref "U30") (pin "7") (pinfunction "NC_7") (pintype "passive"))
    )
    (net (code "57") (name "/USB_TX1_P") (class "Default")
      (node (ref "C158") (pin "2") (pinfunction "2_2") (pintype "passive"))
      (node (ref "J12") (pin "9") (pinfunction "TX+_9") (pintype "passive"))
      (node (ref "U30") (pin "5") (pinfunction "I/O_5") (pintype "passive"))
      (node (ref "U30") (pin "6") (pinfunction "NC_6") (pintype "passive"))
    )
    (net (code "58") (name "/USB_TX2_N") (class "Default")
      (node (ref "C174") (pin "2") (pinfunction "2_2") (pintype "passive"))
      (node (ref "J13") (pin "8") (pinfunction "TX-_8") (pintype "passive"))
      (node (ref "U32") (pin "4") (pinfunction "I/O_4") (pintype "passive"))
      (node (ref "U32") (pin "7") (pinfunction "NC_7") (pintype "passive"))
    )
    (net (code "59") (name "/USB_TX2_P") (class "Default")
      (node (ref "C175") (pin "2") (pinfunction "2_2") (pintype "passive"))
      (node (ref "J13") (pin "9") (pinfunction "TX+_9") (pintype "passive"))
      (node (ref "U32") (pin "5") (pinfunction "I/O_5") (pintype "passive"))
      (node (ref "U32") (pin "6") (pinfunction "NC_6") (pintype "passive"))
    )
    (net (code "60") (name "/VBUS") (class "Default")
      (node (ref "R192") (pin "2") (pinfunction "2_2") (pintype "passive"))
      (node (ref "R193") (pin "2") (pinfunction "2_2") (pintype "passive"))
      (node (ref "U33") (pin "25") (pinfunction "VBUS_25") (pintype "passive"))
    )
    (net (code "61") (name "/VP12") (class "Default")
      (node (ref "C183") (pin "1") (pinfunction "1_1") (pintype "passive"))
      (node (ref "C184") (pin "1") (pinfunction "1_1") (pintype "passive"))
      (node (ref "C185") (pin "1") (pinfunction "1_1") (pintype "passive"))
      (node (ref "C186") (pin "1") (pinfunction "1_1") (pintype "passive"))
      (node (ref "C187") (pin "1") (pinfunction "1_1") (pintype "passive"))
      (node (ref "C188") (pin "1") (pinfunction "1_1") (pintype "passive"))
      (node (ref "C189") (pin "1") (pinfunction "1_1") (pintype "passive"))
      (node (ref "L18") (pin "2") (pinfunction "2_2") (pintype "passive"))
      (node (ref "U33") (pin "13") (pinfunction "VP12_P4_13") (pintype "passive"))
      (node (ref "U33") (pin "3") (pinfunction "VP12_P3_3") (pintype "passive"))
      (node (ref "U33") (pin "40") (pinfunction "VP12_P0_40") (pintype "passive"))
      (node (ref "U33") (pin "46") (pinfunction "AVDD12_46") (pintype "passive"))
      (node (ref "U33") (pin "49") (pinfunction "VP12_P1_49") (pintype "passive"))
      (node (ref "U33") (pin "58") (pinfunction "VP12_P2_58") (pintype "passive"))
    )
    (net (code "62") (name "/X1") (class "Default")
      (node (ref "C200") (pin "2") (pinfunction "2_2") (pintype "passive"))
      (node (ref "R184") (pin "2") (pinfunction "2_2") (pintype "passive"))
      (node (ref "U33") (pin "45") (pinfunction "X1_45") (pintype "passive"))
      (node (ref "Y2") (pin "3") (pinfunction "X2_3") (pintype "passive"))
    )
    (net (code "63") (name "/X2") (class "Default")
      (node (ref "C199") (pin "2") (pinfunction "2_2") (pintype "passive"))
      (node (ref "R183") (pin "1") (pinfunction "1_1") (pintype "passive"))
      (node (ref "U33") (pin "44") (pinfunction "X2_44") (pintype "passive"))
      (node (ref "Y2") (pin "1") (pinfunction "X1_1") (pintype "passive"))
    )
    (net (code "64") (name "EARTH") (class "Default")
      (node (ref "C190") (pin "2") (pinfunction "2_2") (pintype "passive"))
      (node (ref "J12") (pin "10") (pinfunction "SHELL1_10") (pintype "passive"))
      (node (ref "J13") (pin "10") (pinfunction "SHELL1_10") (pintype "passive"))
      (node (ref "R182") (pin "2") (pinfunction "2_2") (pintype "passive"))
    )
    (net (code "65") (name "GND") (class "Default")
      (node (ref "C152") (pin "1") (pinfunction "1_1") (pintype "passive"))
      (node (ref "C153") (pin "2") (pinfunction "2_2") (pintype "passive"))
      (node (ref "C154") (pin "1") (pinfunction "1_1") (pintype "passive"))
      (node (ref "C155") (pin "2") (pinfunction "2_2") (pintype "passive"))
      (node (ref "C159") (pin "2") (pinfunction "2_2") (pintype "passive"))
      (node (ref "C160") (pin "1") (pinfunction "1_1") (pintype "passive"))
      (node (ref "C161") (pin "1") (pinfunction "1_1") (pintype "passive"))
      (node (ref "C164") (pin "1") (pinfunction "1_1") (pintype "passive"))
      (node (ref "C165") (pin "1") (pinfunction "1_1") (pintype "passive"))
      (node (ref "C166") (pin "2") (pinfunction "2_2") (pintype "passive"))
      (node (ref "C167") (pin "2") (pinfunction "2_2") (pintype "passive"))
      (node (ref "C168") (pin "2") (pinfunction "2_2") (pintype "passive"))
      (node (ref "C169") (pin "2") (pinfunction "2_2") (pintype "passive"))
      (node (ref "C170") (pin "2") (pinfunction "2_2") (pintype "passive"))
      (node (ref "C171") (pin "2") (pinfunction "2_2") (pintype "passive"))
      (node (ref "C172") (pin "2") (pinfunction "2_2") (pintype "passive"))
      (node (ref "C173") (pin "1") (pinfunction "1_1") (pintype "passive"))
      (node (ref "C176") (pin "2") (pinfunction "2_2") (pintype "passive"))
      (node (ref "C177") (pin "1") (pinfunction "1_1") (pintype "passive"))
      (node (ref "C178") (pin "1") (pinfunction "1_1") (pintype "passive"))
      (node (ref "C179") (pin "2") (pinfunction "2_2") (pintype "passive"))
      (node (ref "C180") (pin "2") (pinfunction "2_2") (pintype "passive"))
      (node (ref "C181") (pin "2") (pinfunction "2_2") (pintype "passive"))
      (node (ref "C182") (pin "2") (pinfunction "2_2") (pintype "passive"))
      (node (ref "C183") (pin "2") (pinfunction "2_2") (pintype "passive"))
      (node (ref "C184") (pin "2") (pinfunction "2_2") (pintype "passive"))
      (node (ref "C185") (pin "2") (pinfunction "2_2") (pintype "passive"))
      (node (ref "C186") (pin "2") (pinfunction "2_2") (pintype "passive"))
      (node (ref "C187") (pin "2") (pinfunction "2_2") (pintype "passive"))
      (node (ref "C188") (pin "2") (pinfunction "2_2") (pintype "passive"))
      (node (ref "C189") (pin "2") (pinfunction "2_2") (pintype "passive"))
      (node (ref "C190") (pin "1") (pinfunction "1_1") (pintype "passive"))
      (node (ref "C191") (pin "2") (pinfunction "2_2") (pintype "passive"))
      (node (ref "C192") (pin "1") (pinfunction "1_1") (pintype "passive"))
      (node (ref "C199") (pin "1") (pinfunction "1_1") (pintype "passive"))
      (node (ref "C200") (pin "1") (pinfunction "1_1") (pintype "passive"))
      (node (ref "C201") (pin "1") (pinfunction "1_1") (pintype "passive"))
      (node (ref "C202") (pin "1") (pinfunction "1_1") (pintype "passive"))
      (node (ref "D76") (pin "1") (pintype "passive"))
      (node (ref "D77") (pin "1") (pintype "passive"))
      (node (ref "J12") (pin "4") (pinfunction "GND_4") (pintype "passive"))
      (node (ref "J12") (pin "7") (pinfunction "GND_7") (pintype "passive"))
      (node (ref "J13") (pin "4") (pinfunction "GND_4") (pintype "passive"))
      (node (ref "J13") (pin "7") (pinfunction "GND_7") (pintype "passive"))
      (node (ref "R175") (pin "1") (pinfunction "1_1") (pintype "passive"))
      (node (ref "R182") (pin "1") (pinfunction "1_1") (pintype "passive"))
      (node (ref "R193") (pin "1") (pinfunction "1_1") (pintype "passive"))
      (node (ref "R195") (pin "1") (pinfunction "1_1") (pintype "passive"))
      (node (ref "R197") (pin "2") (pinfunction "2_2") (pintype "passive"))
      (node (ref "R200") (pin "1") (pinfunction "1_1") (pintype "passive"))
      (node (ref "R202") (pin "2") (pinfunction "2_2") (pintype "passive"))
      (node (ref "U30") (pin "3") (pinfunction "GND_3") (pintype "passive"))
      (node (ref "U30") (pin "8") (pinfunction "GND_8") (pintype "passive"))
      (node (ref "U31") (pin "6") (pinfunction "GND_6") (pintype "passive"))
      (node (ref "U32") (pin "3") (pinfunction "GND_3") (pintype "passive"))
      (node (ref "U32") (pin "8") (pinfunction "GND_8") (pintype "passive"))
      (node (ref "U33") (pin "18") (pinfunction "VSSP_18") (pintype "passive"))
      (node (ref "U33") (pin "65") (pinfunction "EP_65") (pintype "passive"))
      (node (ref "Y2") (pin "2") (pinfunction "NC_2") (pintype "passive"))
      (node (ref "Y2") (pin "4") (pinfunction "NC_4") (pintype "passive"))
    )
    (net (code "66") (name "Net-(C173-Pad2)") (class "Default")
      (node (ref "C173") (pin "2") (pinfunction "2_2") (pintype "passive"))
      (node (ref "R172") (pin "1") (pinfunction "1_1") (pintype "passive"))
    )
    (net (code "67") (name "Net-(L14-Pad1)") (class "Default")
      (node (ref "L14") (pin "1") (pintype "passive"))
      (node (ref "R168") (pin "2") (pinfunction "2_2") (pintype "passive"))
      (node (ref "R170") (pin "1") (pinfunction "1_1") (pintype "passive"))
    )
    (net (code "68") (name "Net-(L14-Pad4)") (class "Default")
      (node (ref "L14") (pin "4") (pintype "passive"))
      (node (ref "R164") (pin "1") (pinfunction "1_1") (pintype "passive"))
      (node (ref "R166") (pin "2") (pinfunction "2_2") (pintype "passive"))
    )
    (net (code "69") (name "Net-(L19-Pad1)") (class "Default")
      (node (ref "L19") (pin "1") (pintype "passive"))
      (node (ref "R180") (pin "2") (pinfunction "2_2") (pintype "passive"))
      (node (ref "R181") (pin "1") (pinfunction "1_1") (pintype "passive"))
    )
    (net (code "70") (name "Net-(L19-Pad4)") (class "Default")
      (node (ref "L19") (pin "4") (pintype "passive"))
      (node (ref "R178") (pin "1") (pinfunction "1_1") (pintype "passive"))
      (node (ref "R179") (pin "2") (pinfunction "2_2") (pintype "passive"))
    )
    (net (code "71") (name "Net-(R183-Pad2)") (class "Default")
      (node (ref "R183") (pin "2") (pinfunction "2_2") (pintype "passive"))
      (node (ref "R184") (pin "1") (pinfunction "1_1") (pintype "passive"))
    )
    (net (code "72") (name "USB3.0_A") (class "Default")
      (node (ref "C159") (pin "1") (pinfunction "1_1") (pintype "passive"))
      (node (ref "C160") (pin "2") (pinfunction "2_2") (pintype "passive"))
      (node (ref "C161") (pin "2") (pinfunction "2_2") (pintype "passive"))
      (node (ref "D76") (pin "4") (pintype "passive"))
      (node (ref "J12") (pin "1") (pinfunction "VBUS_1") (pintype "passive"))
      (node (ref "L16") (pin "2") (pinfunction "2_2") (pintype "passive"))
      (node (ref "U31") (pin "8") (pinfunction "OUTA_8") (pintype "passive"))
    )
    (net (code "73") (name "USB3.0_B") (class "Default")
      (node (ref "C176") (pin "1") (pinfunction "1_1") (pintype "passive"))
      (node (ref "C177") (pin "2") (pinfunction "2_2") (pintype "passive"))
      (node (ref "C178") (pin "2") (pinfunction "2_2") (pintype "passive"))
      (node (ref "D77") (pin "4") (pintype "passive"))
      (node (ref "J13") (pin "1") (pinfunction "VBUS_1") (pintype "passive"))
      (node (ref "L17") (pin "2") (pinfunction "2_2") (pintype "passive"))
      (node (ref "U31") (pin "5") (pinfunction "OUTB_5") (pintype "passive"))
    )
    (net (code "74") (name "V5") (class "Default")
      (node (ref "C154") (pin "2") (pinfunction "2_2") (pintype "passive"))
      (node (ref "C155") (pin "1") (pinfunction "1_1") (pintype "passive"))
      (node (ref "C191") (pin "1") (pinfunction "1_1") (pintype "passive"))
      (node (ref "C192") (pin "2") (pinfunction "2_2") (pintype "passive"))
      (node (ref "L13") (pin "2") (pinfunction "2_2") (pintype "passive"))
      (node (ref "R160") (pin "2") (pinfunction "2_2") (pintype "passive"))
      (node (ref "R192") (pin "1") (pinfunction "1_1") (pintype "passive"))
      (node (ref "R196") (pin "2") (pinfunction "2_2") (pintype "passive"))
      (node (ref "U33") (pin "20") (pinfunction "VDDP/V5_20") (pintype "passive"))
    )
    (net (code "75") (name "V33") (class "Default")
      (node (ref "C166") (pin "1") (pinfunction "1_1") (pintype "passive"))
      (node (ref "C167") (pin "1") (pinfunction "1_1") (pintype "passive"))
      (node (ref "C168") (pin "1") (pinfunction "1_1") (pintype "passive"))
      (node (ref "C169") (pin "1") (pinfunction "1_1") (pintype "passive"))
      (node (ref "C170") (pin "1") (pinfunction "1_1") (pintype "passive"))
      (node (ref "C171") (pin "1") (pinfunction "1_1") (pintype "passive"))
      (node (ref "C172") (pin "1") (pinfunction "1_1") (pintype "passive"))
      (node (ref "R158") (pin "2") (pinfunction "2_2") (pintype "passive"))
      (node (ref "R173") (pin "1") (pinfunction "1_1") (pintype "passive"))
      (node (ref "R174") (pin "1") (pinfunction "1_1") (pintype "passive"))
      (node (ref "R189") (pin "2") (pinfunction "2_2") (pintype "passive"))
      (node (ref "R194") (pin "2") (pinfunction "2_2") (pintype "passive"))
      (node (ref "R201") (pin "1") (pinfunction "1_1") (pintype "passive"))
      (node (ref "U33") (pin "21") (pinfunction "V33_21") (pintype "passive"))
      (node (ref "U33") (pin "26") (pinfunction "DVDD33_26") (pintype "passive"))
      (node (ref "U33") (pin "35") (pinfunction "AVDD33_35") (pintype "passive"))
      (node (ref "U33") (pin "43") (pinfunction "AVDD33_43") (pintype "passive"))
      (node (ref "U33") (pin "54") (pinfunction "AVDD33_54") (pintype "passive"))
      (node (ref "U33") (pin "62") (pinfunction "DVDD33_62") (pintype "passive"))
      (node (ref "U33") (pin "8") (pinfunction "AVDD33_8") (pintype "passive"))
    )
    (net (code "76") (name "VCC_3V3") (class "Default")
      (node (ref "R158") (pin "1") (pinfunction "1_1") (pintype "passive"))
      (node (ref "R160") (pin "1") (pinfunction "1_1") (pintype "passive"))
    )
    (net (code "77") (name "VCC_5V") (class "Default")
      (node (ref "C152") (pin "2") (pinfunction "2_2") (pintype "passive"))
      (node (ref "C153") (pin "1") (pinfunction "1_1") (pintype "passive"))
      (node (ref "C164") (pin "2") (pinfunction "2_2") (pintype "passive"))
      (node (ref "L13") (pin "1") (pinfunction "1_1") (pintype "passive"))
      (node (ref "L16") (pin "1") (pinfunction "1_1") (pintype "passive"))
      (node (ref "L17") (pin "1") (pinfunction "1_1") (pintype "passive"))
      (node (ref "U31") (pin "7") (pinfunction "IN_7") (pintype "passive"))
    )
    (net (code "78") (name "unconnected-(U33-P_SPI_CK-Pad29)") (class "Default")
      (node (ref "U33") (pin "29") (pinfunction "P_SPI_CK_29") (pintype "passive+no_connect"))
    )
    (net (code "79") (name "unconnected-(U33-P_SPI_CZ-Pad31)") (class "Default")
      (node (ref "U33") (pin "31") (pinfunction "P_SPI_CZ_31") (pintype "passive+no_connect"))
    )
    (net (code "80") (name "unconnected-(U33-P_SPI_DI-Pad30)") (class "Default")
      (node (ref "U33") (pin "30") (pinfunction "P_SPI_DI_30") (pintype "passive+no_connect"))
    )
    (net (code "81") (name "unconnected-(U33-P_SPI_DO-Pad28)") (class "Default")
      (node (ref "U33") (pin "28") (pinfunction "P_SPI_DO_28") (pintype "passive+no_connect"))
    )
  )
)
